# IRQF103C8.net
KiCad netlist of a schematic drawn in EAGLE
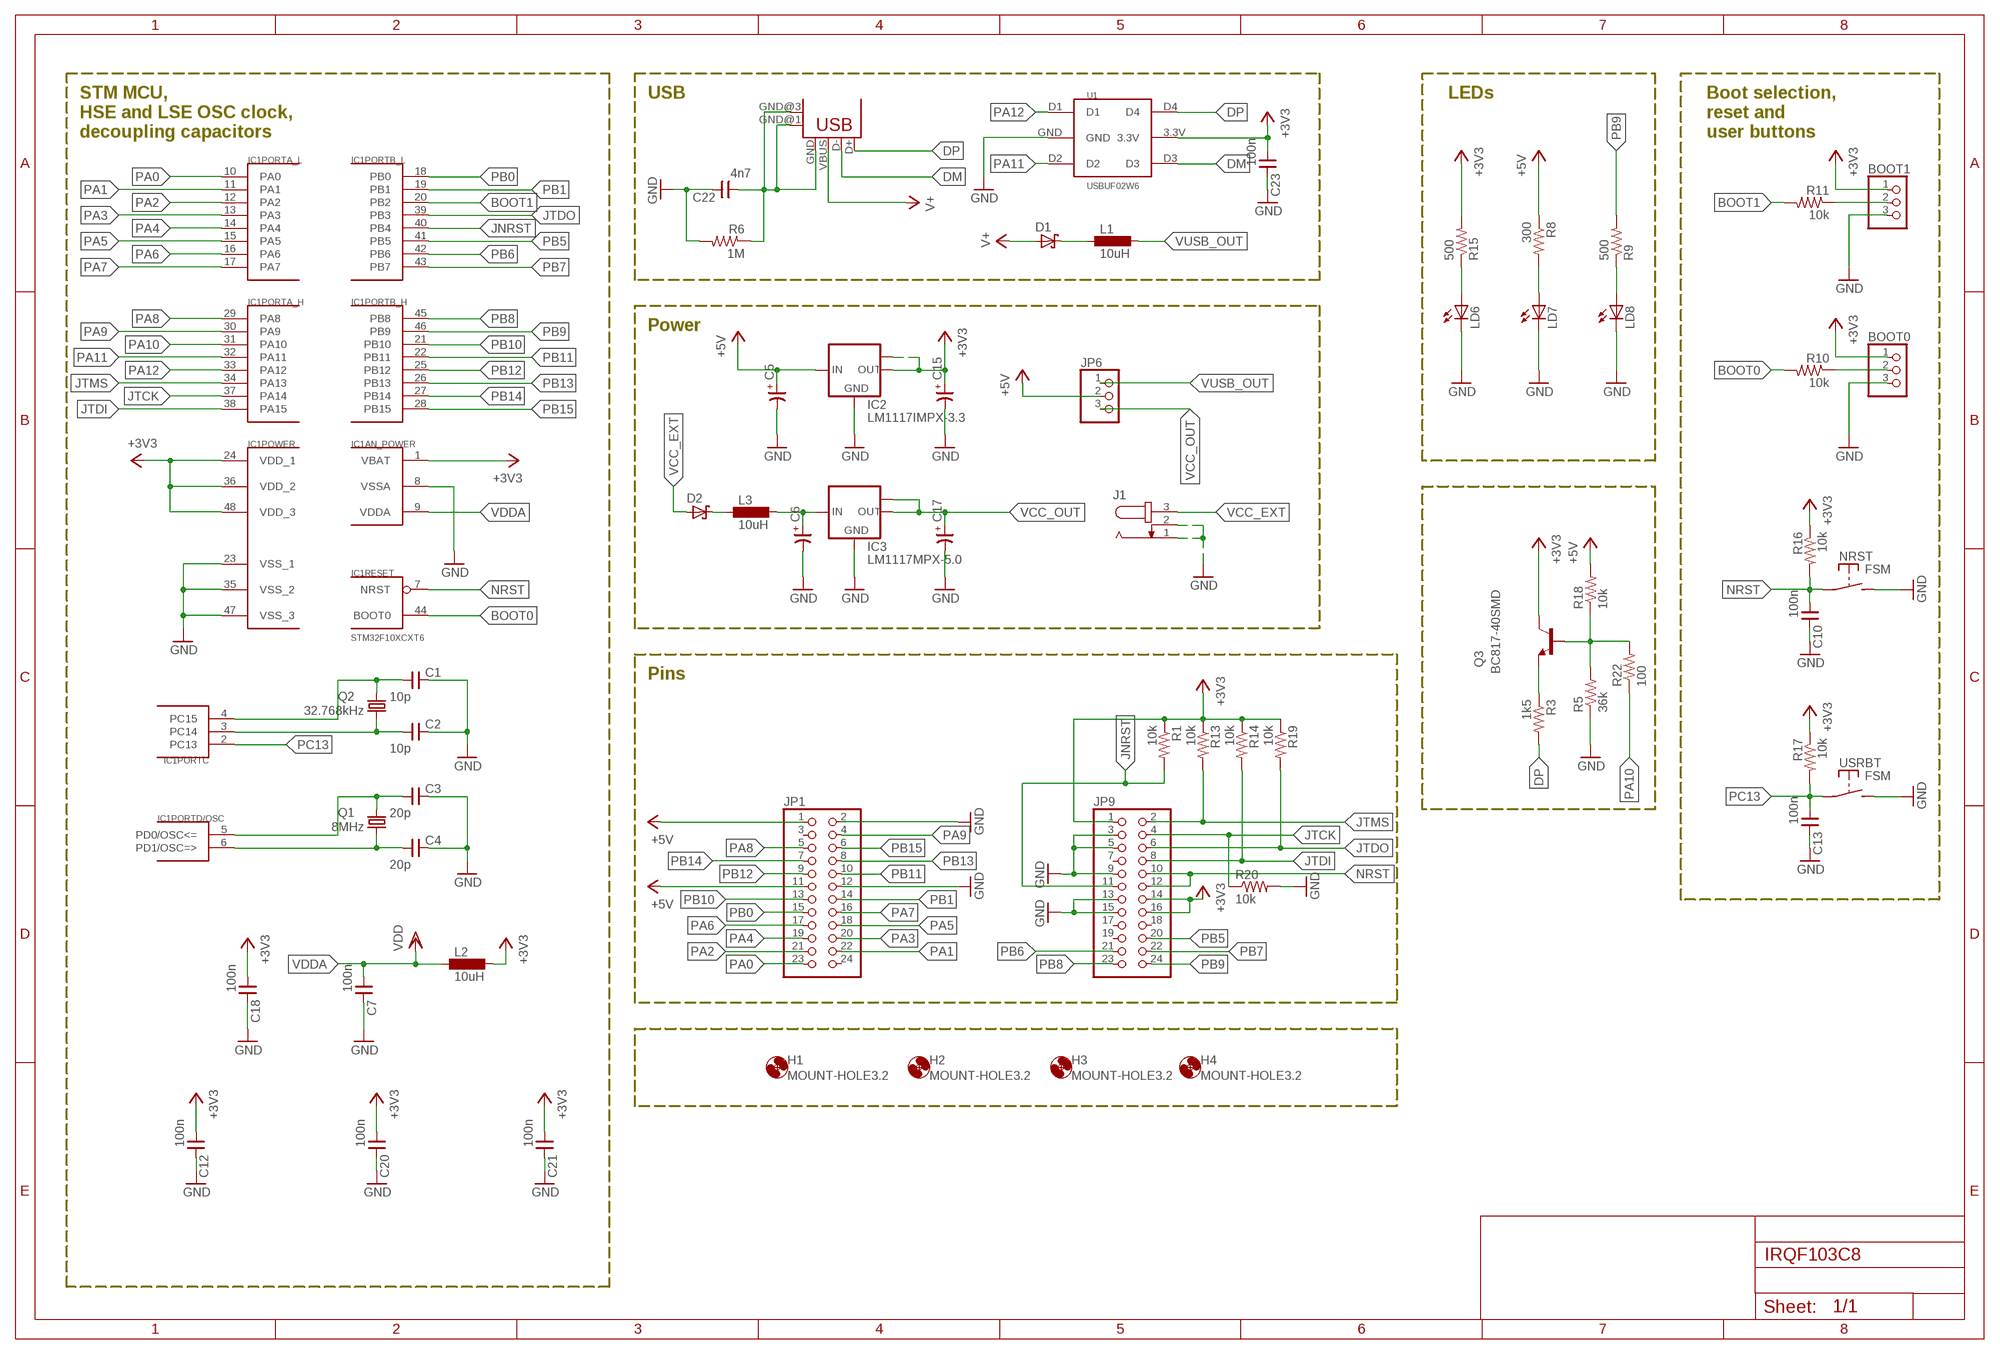
[diagram p0: schematic, sheet 1]

(export (version "E")
  (design (tool "Eeschema 10.0.6"))
  (components
    (comp (ref "BOOT0")
      (value "PINHD-1X3")
      (footprint "eagle-import:1X03")
      (libsource (lib "eagle-import") (part "PINHD-1X3"))
    )
    (comp (ref "BOOT1")
      (value "PINHD-1X3")
      (footprint "eagle-import:1X03")
      (libsource (lib "eagle-import") (part "PINHD-1X3"))
    )
    (comp (ref "C1")
      (value "10p")
      (footprint "eagle-import:0805")
      (libsource (lib "eagle-import") (part "CNP-0805"))
    )
    (comp (ref "C2")
      (value "10p")
      (footprint "eagle-import:0805")
      (libsource (lib "eagle-import") (part "CNP-0805"))
    )
    (comp (ref "C3")
      (value "20p")
      (footprint "eagle-import:0805")
      (libsource (lib "eagle-import") (part "CNP-0805"))
    )
    (comp (ref "C4")
      (value "20p")
      (footprint "eagle-import:0805")
      (libsource (lib "eagle-import") (part "CNP-0805"))
    )
    (comp (ref "C5")
      (value "CP-3258-TE-B")
      (footprint "eagle-import:3528-TE-B")
      (libsource (lib "eagle-import") (part "CP-3258-TE-B"))
    )
    (comp (ref "C6")
      (value "CP-3258-TE-B")
      (footprint "eagle-import:3528-TE-B")
      (libsource (lib "eagle-import") (part "CP-3258-TE-B"))
    )
    (comp (ref "C7")
      (value "100n")
      (footprint "eagle-import:0805")
      (libsource (lib "eagle-import") (part "CNP-0805"))
    )
    (comp (ref "C10")
      (value "100n")
      (footprint "eagle-import:0805")
      (libsource (lib "eagle-import") (part "CNP-0805"))
    )
    (comp (ref "C12")
      (value "100n")
      (footprint "eagle-import:0805")
      (libsource (lib "eagle-import") (part "CNP-0805"))
    )
    (comp (ref "C13")
      (value "100n")
      (footprint "eagle-import:0805")
      (libsource (lib "eagle-import") (part "CNP-0805"))
    )
    (comp (ref "C15")
      (value "CP-3216-TE-A")
      (footprint "eagle-import:3216-TE-A")
      (libsource (lib "eagle-import") (part "CP-3216-TE-A"))
    )
    (comp (ref "C17")
      (value "CP-3216-TE-A")
      (footprint "eagle-import:3216-TE-A")
      (libsource (lib "eagle-import") (part "CP-3216-TE-A"))
    )
    (comp (ref "C18")
      (value "100n")
      (footprint "eagle-import:0805")
      (libsource (lib "eagle-import") (part "CNP-0805"))
    )
    (comp (ref "C20")
      (value "100n")
      (footprint "eagle-import:0805")
      (libsource (lib "eagle-import") (part "CNP-0805"))
    )
    (comp (ref "C21")
      (value "100n")
      (footprint "eagle-import:0805")
      (libsource (lib "eagle-import") (part "CNP-0805"))
    )
    (comp (ref "C22")
      (value "4n7")
      (footprint "eagle-import:0805")
      (libsource (lib "eagle-import") (part "CNP-0805"))
    )
    (comp (ref "C23")
      (value "100n")
      (footprint "eagle-import:0805")
      (libsource (lib "eagle-import") (part "CNP-0805"))
    )
    (comp (ref "D1")
      (value "SCHOTTKY_SMA")
      (footprint "eagle-import:DIOM5326X292N")
      (libsource (lib "eagle-import") (part "SCHOTTKY_SMA"))
    )
    (comp (ref "D2")
      (value "SCHOTTKY_SMA")
      (footprint "eagle-import:DIOM5326X292N")
      (libsource (lib "eagle-import") (part "SCHOTTKY_SMA"))
    )
    (comp (ref "H1")
      (value "MOUNT-HOLE3.2")
      (footprint "eagle-import:3,2")
      (libsource (lib "eagle-import") (part "MOUNT-HOLE3.2"))
    )
    (comp (ref "H2")
      (value "MOUNT-HOLE3.2")
      (footprint "eagle-import:3,2")
      (libsource (lib "eagle-import") (part "MOUNT-HOLE3.2"))
    )
    (comp (ref "H3")
      (value "MOUNT-HOLE3.2")
      (footprint "eagle-import:3,2")
      (libsource (lib "eagle-import") (part "MOUNT-HOLE3.2"))
    )
    (comp (ref "H4")
      (value "MOUNT-HOLE3.2")
      (footprint "eagle-import:3,2")
      (libsource (lib "eagle-import") (part "MOUNT-HOLE3.2"))
    )
    (comp (ref "IC1")
      (value "STM32F10XCXT6")
      (footprint "eagle-import:TQFP48")
      (libsource (lib "eagle-import") (part "STM32F10XCXT6"))
    )
    (comp (ref "IC2")
      (value "LM1117IMPX-3.3")
      (footprint "eagle-import:SOT223")
      (libsource (lib "eagle-import") (part "LM1117IMPX-3.3"))
    )
    (comp (ref "IC3")
      (value "LM1117MPX-5.0")
      (footprint "eagle-import:SOT223")
      (libsource (lib "eagle-import") (part "LM1117MPX-5.0"))
    )
    (comp (ref "J1")
      (value "JACK-PLUG1")
      (footprint "eagle-import:SPC4078")
      (libsource (lib "eagle-import") (part "JACK-PLUG1"))
    )
    (comp (ref "JP1")
      (value "PINHD-2X12")
      (footprint "eagle-import:2X12")
      (libsource (lib "eagle-import") (part "PINHD-2X12"))
    )
    (comp (ref "JP6")
      (value "PINHD-1X3")
      (footprint "eagle-import:1X03")
      (libsource (lib "eagle-import") (part "PINHD-1X3"))
    )
    (comp (ref "JP9")
      (value "PINHD-2X12")
      (footprint "eagle-import:2X12")
      (libsource (lib "eagle-import") (part "PINHD-2X12"))
    )
    (comp (ref "L1")
      (value "10uH")
      (footprint "eagle-import:INDC1608X95N")
      (libsource (lib "eagle-import") (part "INDUCTOR_0603"))
    )
    (comp (ref "L2")
      (value "10uH")
      (footprint "eagle-import:INDC1608X95N")
      (libsource (lib "eagle-import") (part "INDUCTOR_0603"))
    )
    (comp (ref "L3")
      (value "10uH")
      (footprint "eagle-import:INDC1608X95N")
      (libsource (lib "eagle-import") (part "INDUCTOR_0603"))
    )
    (comp (ref "LD6")
      (value "LEDCHIPLED_0805")
      (footprint "eagle-import:CHIPLED_0805")
      (libsource (lib "eagle-import") (part "LEDCHIPLED_0805"))
    )
    (comp (ref "LD7")
      (value "LEDCHIPLED_0805")
      (footprint "eagle-import:CHIPLED_0805")
      (libsource (lib "eagle-import") (part "LEDCHIPLED_0805"))
    )
    (comp (ref "LD8")
      (value "LEDCHIPLED_0805")
      (footprint "eagle-import:CHIPLED_0805")
      (libsource (lib "eagle-import") (part "LEDCHIPLED_0805"))
    )
    (comp (ref "NRST")
      (value "FSM")
      (footprint "eagle-import:FSM")
      (libsource (lib "eagle-import") (part "FSM"))
    )
    (comp (ref "Q1")
      (value "8MHz")
      (footprint "eagle-import:HC49_S")
      (libsource (lib "eagle-import") (part "CRYTALHC49S"))
    )
    (comp (ref "Q2")
      (value "32.768kHz")
      (footprint "eagle-import:TC26H")
      (libsource (lib "eagle-import") (part "CRYTALTC26H"))
    )
    (comp (ref "Q3")
      (value "BC817-40SMD")
      (footprint "eagle-import:SOT23-BEC")
      (libsource (lib "eagle-import") (part "BC817SMD-40"))
    )
    (comp (ref "R1")
      (value "10k")
      (footprint "eagle-import:M0805")
      (libsource (lib "eagle-import") (part "R-US_M0805"))
    )
    (comp (ref "R3")
      (value "1k5")
      (footprint "eagle-import:M0805")
      (libsource (lib "eagle-import") (part "R-US_M0805"))
    )
    (comp (ref "R5")
      (value "36k")
      (footprint "eagle-import:M0805")
      (libsource (lib "eagle-import") (part "R-US_M0805"))
    )
    (comp (ref "R6")
      (value "1M")
      (footprint "eagle-import:M0805")
      (libsource (lib "eagle-import") (part "R-US_M0805"))
    )
    (comp (ref "R8")
      (value "300")
      (footprint "eagle-import:M0805")
      (libsource (lib "eagle-import") (part "R-US_M0805"))
    )
    (comp (ref "R9")
      (value "500")
      (footprint "eagle-import:M0805")
      (libsource (lib "eagle-import") (part "R-US_M0805"))
    )
    (comp (ref "R10")
      (value "10k")
      (footprint "eagle-import:M0805")
      (libsource (lib "eagle-import") (part "R-US_M0805"))
    )
    (comp (ref "R11")
      (value "10k")
      (footprint "eagle-import:M0805")
      (libsource (lib "eagle-import") (part "R-US_M0805"))
    )
    (comp (ref "R13")
      (value "10k")
      (footprint "eagle-import:M0805")
      (libsource (lib "eagle-import") (part "R-US_M0805"))
    )
    (comp (ref "R14")
      (value "10k")
      (footprint "eagle-import:M0805")
      (libsource (lib "eagle-import") (part "R-US_M0805"))
    )
    (comp (ref "R15")
      (value "500")
      (footprint "eagle-import:M0805")
      (libsource (lib "eagle-import") (part "R-US_M0805"))
    )
    (comp (ref "R16")
      (value "10k")
      (footprint "eagle-import:M0805")
      (libsource (lib "eagle-import") (part "R-US_M0805"))
    )
    (comp (ref "R17")
      (value "10k")
      (footprint "eagle-import:M0805")
      (libsource (lib "eagle-import") (part "R-US_M0805"))
    )
    (comp (ref "R18")
      (value "10k")
      (footprint "eagle-import:M0805")
      (libsource (lib "eagle-import") (part "R-US_M0805"))
    )
    (comp (ref "R19")
      (value "10k")
      (footprint "eagle-import:M0805")
      (libsource (lib "eagle-import") (part "R-US_M0805"))
    )
    (comp (ref "R20")
      (value "10k")
      (footprint "eagle-import:M0805")
      (libsource (lib "eagle-import") (part "R-US_M0805"))
    )
    (comp (ref "R22")
      (value "100")
      (footprint "eagle-import:M0805")
      (libsource (lib "eagle-import") (part "R-US_M0805"))
    )
    (comp (ref "U1")
      (value "USBUF02W6")
      (footprint "eagle-import:SOT23-6L")
      (libsource (lib "eagle-import") (part "USBUF02W6"))
    )
    (comp (ref "USB1")
      (value "USB-MB-S")
      (footprint "eagle-import:USB-MB-S")
      (libsource (lib "eagle-import") (part "USB-MB-S"))
    )
    (comp (ref "USRBT")
      (value "FSM")
      (footprint "eagle-import:FSM")
      (libsource (lib "eagle-import") (part "FSM"))
    )
  )
  (nets
    (net (code "1") (name "+3V3") (class "Default")
      (node (ref "BOOT0") (pin "1") (pinfunction "1_1") (pintype "passive"))
      (node (ref "BOOT1") (pin "1") (pinfunction "1_1") (pintype "passive"))
      (node (ref "C12") (pin "1") (pinfunction "1_1") (pintype "passive"))
      (node (ref "C15") (pin "+") (pinfunction "+_+") (pintype "passive"))
      (node (ref "C18") (pin "1") (pinfunction "1_1") (pintype "passive"))
      (node (ref "C20") (pin "1") (pinfunction "1_1") (pintype "passive"))
      (node (ref "C21") (pin "1") (pinfunction "1_1") (pintype "passive"))
      (node (ref "C23") (pin "1") (pinfunction "1_1") (pintype "passive"))
      (node (ref "IC1") (pin "1") (pinfunction "VBAT_1") (pintype "power_in"))
      (node (ref "IC1") (pin "24") (pinfunction "VDD_1_24") (pintype "power_in"))
      (node (ref "IC1") (pin "36") (pinfunction "VDD_2_36") (pintype "power_in"))
      (node (ref "IC1") (pin "48") (pinfunction "VDD_3_48") (pintype "power_in"))
      (node (ref "IC2") (pin "2") (pinfunction "OUT_2") (pintype "passive"))
      (node (ref "IC2") (pin "TAB") (pinfunction "OUT1_TAB") (pintype "passive"))
      (node (ref "JP9") (pin "1") (pinfunction "1_1") (pintype "passive"))
      (node (ref "JP9") (pin "14") (pinfunction "14_14") (pintype "passive"))
      (node (ref "JP9") (pin "16") (pinfunction "16_16") (pintype "passive"))
      (node (ref "L2") (pin "2") (pinfunction "2_2") (pintype "passive"))
      (node (ref "Q3") (pin "C") (pinfunction "C_C") (pintype "passive"))
      (node (ref "R1") (pin "1") (pinfunction "1_1") (pintype "passive"))
      (node (ref "R13") (pin "1") (pinfunction "1_1") (pintype "passive"))
      (node (ref "R14") (pin "1") (pinfunction "1_1") (pintype "passive"))
      (node (ref "R15") (pin "2") (pinfunction "2_2") (pintype "passive"))
      (node (ref "R16") (pin "1") (pinfunction "1_1") (pintype "passive"))
      (node (ref "R17") (pin "1") (pinfunction "1_1") (pintype "passive"))
      (node (ref "R19") (pin "1") (pinfunction "1_1") (pintype "passive"))
      (node (ref "U1") (pin "3.3V") (pinfunction "3.3V_3.3V") (pintype "bidirectional"))
    )
    (net (code "2") (name "+5V") (class "Default")
      (node (ref "C5") (pin "+") (pinfunction "+_+") (pintype "passive"))
      (node (ref "IC2") (pin "3") (pinfunction "IN_3") (pintype "input"))
      (node (ref "JP1") (pin "1") (pinfunction "1_1") (pintype "passive"))
      (node (ref "JP1") (pin "11") (pinfunction "11_11") (pintype "passive"))
      (node (ref "JP6") (pin "2") (pinfunction "2_2") (pintype "passive"))
      (node (ref "R18") (pin "2") (pinfunction "2_2") (pintype "passive"))
      (node (ref "R8") (pin "1") (pinfunction "1_1") (pintype "passive"))
    )
    (net (code "3") (name "BOOT0") (class "Default")
      (node (ref "IC1") (pin "44") (pinfunction "BOOT0_44") (pintype "input"))
      (node (ref "R10") (pin "2") (pinfunction "2_2") (pintype "passive"))
    )
    (net (code "4") (name "BOOT1") (class "Default")
      (node (ref "IC1") (pin "20") (pinfunction "PB2_20") (pintype "bidirectional"))
      (node (ref "R11") (pin "2") (pinfunction "2_2") (pintype "passive"))
    )
    (net (code "5") (name "DM") (class "Default")
      (node (ref "U1") (pin "D3") (pinfunction "D3_D3") (pintype "bidirectional"))
      (node (ref "USB1") (pin "D-") (pinfunction "D-_D-") (pintype "bidirectional"))
    )
    (net (code "6") (name "DP") (class "Default")
      (node (ref "R3") (pin "2") (pinfunction "2_2") (pintype "passive"))
      (node (ref "U1") (pin "D4") (pinfunction "D4_D4") (pintype "bidirectional"))
      (node (ref "USB1") (pin "D+") (pinfunction "D+_D+") (pintype "bidirectional"))
    )
    (net (code "7") (name "GND") (class "Default")
      (node (ref "BOOT0") (pin "3") (pinfunction "3_3") (pintype "passive"))
      (node (ref "BOOT1") (pin "3") (pinfunction "3_3") (pintype "passive"))
      (node (ref "C1") (pin "2") (pinfunction "2_2") (pintype "passive"))
      (node (ref "C10") (pin "2") (pinfunction "2_2") (pintype "passive"))
      (node (ref "C12") (pin "2") (pinfunction "2_2") (pintype "passive"))
      (node (ref "C13") (pin "2") (pinfunction "2_2") (pintype "passive"))
      (node (ref "C15") (pin "-") (pinfunction "-_-") (pintype "passive"))
      (node (ref "C17") (pin "-") (pinfunction "-_-") (pintype "passive"))
      (node (ref "C18") (pin "2") (pinfunction "2_2") (pintype "passive"))
      (node (ref "C2") (pin "2") (pinfunction "2_2") (pintype "passive"))
      (node (ref "C20") (pin "2") (pinfunction "2_2") (pintype "passive"))
      (node (ref "C21") (pin "2") (pinfunction "2_2") (pintype "passive"))
      (node (ref "C22") (pin "2") (pinfunction "2_2") (pintype "passive"))
      (node (ref "C23") (pin "2") (pinfunction "2_2") (pintype "passive"))
      (node (ref "C3") (pin "2") (pinfunction "2_2") (pintype "passive"))
      (node (ref "C4") (pin "2") (pinfunction "2_2") (pintype "passive"))
      (node (ref "C5") (pin "-") (pinfunction "-_-") (pintype "passive"))
      (node (ref "C6") (pin "-") (pinfunction "-_-") (pintype "passive"))
      (node (ref "C7") (pin "2") (pinfunction "2_2") (pintype "passive"))
      (node (ref "IC1") (pin "23") (pinfunction "VSS_1_23") (pintype "power_in"))
      (node (ref "IC1") (pin "35") (pinfunction "VSS_2_35") (pintype "power_in"))
      (node (ref "IC1") (pin "47") (pinfunction "VSS_3_47") (pintype "power_in"))
      (node (ref "IC1") (pin "8") (pinfunction "VSSA_8") (pintype "power_in"))
      (node (ref "IC2") (pin "1") (pinfunction "GND_1") (pintype "input"))
      (node (ref "IC3") (pin "1") (pinfunction "GND_1") (pintype "input"))
      (node (ref "J1") (pin "1") (pinfunction "1_1") (pintype "passive"))
      (node (ref "J1") (pin "2") (pinfunction "2_2") (pintype "passive"))
      (node (ref "JP1") (pin "12") (pinfunction "12_12") (pintype "passive"))
      (node (ref "JP1") (pin "2") (pinfunction "2_2") (pintype "passive"))
      (node (ref "JP9") (pin "13") (pinfunction "13_13") (pintype "passive"))
      (node (ref "JP9") (pin "15") (pinfunction "15_15") (pintype "passive"))
      (node (ref "JP9") (pin "3") (pinfunction "3_3") (pintype "passive"))
      (node (ref "JP9") (pin "5") (pinfunction "5_5") (pintype "passive"))
      (node (ref "JP9") (pin "9") (pinfunction "9_9") (pintype "passive"))
      (node (ref "LD6") (pin "C") (pinfunction "C_C") (pintype "passive"))
      (node (ref "LD7") (pin "C") (pinfunction "C_C") (pintype "passive"))
      (node (ref "LD8") (pin "C") (pinfunction "C_C") (pintype "passive"))
      (node (ref "NRST") (pin "P$2") (pinfunction "S_P$2") (pintype "passive"))
      (node (ref "R20") (pin "2") (pinfunction "2_2") (pintype "passive"))
      (node (ref "R5") (pin "1") (pinfunction "1_1") (pintype "passive"))
      (node (ref "R6") (pin "2") (pinfunction "2_2") (pintype "passive"))
      (node (ref "U1") (pin "GND") (pinfunction "GND_GND") (pintype "bidirectional"))
      (node (ref "USRBT") (pin "P$2") (pinfunction "S_P$2") (pintype "passive"))
    )
    (net (code "8") (name "JNRST") (class "Default")
      (node (ref "IC1") (pin "40") (pinfunction "PB4_40") (pintype "bidirectional"))
      (node (ref "JP9") (pin "11") (pinfunction "11_11") (pintype "passive"))
      (node (ref "R1") (pin "2") (pinfunction "2_2") (pintype "passive"))
    )
    (net (code "9") (name "JTCK") (class "Default")
      (node (ref "IC1") (pin "37") (pinfunction "PA14_37") (pintype "bidirectional"))
      (node (ref "JP9") (pin "4") (pinfunction "4_4") (pintype "passive"))
      (node (ref "R20") (pin "1") (pinfunction "1_1") (pintype "passive"))
    )
    (net (code "10") (name "JTDI") (class "Default")
      (node (ref "IC1") (pin "38") (pinfunction "PA15_38") (pintype "bidirectional"))
      (node (ref "JP9") (pin "8") (pinfunction "8_8") (pintype "passive"))
      (node (ref "R14") (pin "2") (pinfunction "2_2") (pintype "passive"))
    )
    (net (code "11") (name "JTDO") (class "Default")
      (node (ref "IC1") (pin "39") (pinfunction "PB3_39") (pintype "bidirectional"))
      (node (ref "JP9") (pin "6") (pinfunction "6_6") (pintype "passive"))
      (node (ref "R19") (pin "2") (pinfunction "2_2") (pintype "passive"))
    )
    (net (code "12") (name "JTMS") (class "Default")
      (node (ref "IC1") (pin "34") (pinfunction "PA13_34") (pintype "bidirectional"))
      (node (ref "JP9") (pin "2") (pinfunction "2_2") (pintype "passive"))
      (node (ref "R13") (pin "2") (pinfunction "2_2") (pintype "passive"))
    )
    (net (code "13") (name "NRST") (class "Default")
      (node (ref "C10") (pin "1") (pinfunction "1_1") (pintype "passive"))
      (node (ref "IC1") (pin "7") (pinfunction "NRST_7") (pintype "input"))
      (node (ref "JP9") (pin "10") (pinfunction "10_10") (pintype "passive"))
      (node (ref "JP9") (pin "12") (pinfunction "12_12") (pintype "passive"))
      (node (ref "NRST") (pin "P$1") (pinfunction "P_P$1") (pintype "passive"))
      (node (ref "R16") (pin "2") (pinfunction "2_2") (pintype "passive"))
    )
    (net (code "14") (name "Net-(BOOT0-Pad2)") (class "Default")
      (node (ref "BOOT0") (pin "2") (pinfunction "2_2") (pintype "passive"))
      (node (ref "R10") (pin "1") (pinfunction "1_1") (pintype "passive"))
    )
    (net (code "15") (name "Net-(BOOT1-Pad2)") (class "Default")
      (node (ref "BOOT1") (pin "2") (pinfunction "2_2") (pintype "passive"))
      (node (ref "R11") (pin "1") (pinfunction "1_1") (pintype "passive"))
    )
    (net (code "16") (name "Net-(C22-Pad1)") (class "Default")
      (node (ref "C22") (pin "1") (pinfunction "1_1") (pintype "passive"))
      (node (ref "R6") (pin "1") (pinfunction "1_1") (pintype "passive"))
      (node (ref "USB1") (pin "GND") (pinfunction "GND_GND") (pintype "bidirectional"))
      (node (ref "USB1") (pin "GND@1") (pinfunction "GND_GND@1") (pintype "bidirectional"))
      (node (ref "USB1") (pin "GND@3") (pinfunction "GND_GND@3") (pintype "bidirectional"))
    )
    (net (code "17") (name "Net-(D1-PadK)") (class "Default")
      (node (ref "D1") (pin "K") (pinfunction "K_K") (pintype "passive"))
      (node (ref "L1") (pin "1") (pinfunction "1_1") (pintype "passive"))
    )
    (net (code "18") (name "Net-(D2-PadK)") (class "Default")
      (node (ref "D2") (pin "K") (pinfunction "K_K") (pintype "passive"))
      (node (ref "L3") (pin "1") (pinfunction "1_1") (pintype "passive"))
    )
    (net (code "19") (name "Net-(IC1F-PC14)") (class "Default")
      (node (ref "C2") (pin "1") (pinfunction "1_1") (pintype "passive"))
      (node (ref "IC1") (pin "3") (pinfunction "PC14_3") (pintype "bidirectional"))
      (node (ref "Q2") (pin "1") (pinfunction "1_1") (pintype "passive"))
    )
    (net (code "20") (name "Net-(IC1F-PC15)") (class "Default")
      (node (ref "C1") (pin "1") (pinfunction "1_1") (pintype "passive"))
      (node (ref "IC1") (pin "4") (pinfunction "PC15_4") (pintype "bidirectional"))
      (node (ref "Q2") (pin "2") (pinfunction "2_2") (pintype "passive"))
    )
    (net (code "21") (name "Net-(IC1G-PD0{slash}OSC<=)") (class "Default")
      (node (ref "C3") (pin "1") (pinfunction "1_1") (pintype "passive"))
      (node (ref "IC1") (pin "5") (pinfunction "PD0/OSC<=_5") (pintype "bidirectional"))
      (node (ref "Q1") (pin "2") (pinfunction "2_2") (pintype "passive"))
    )
    (net (code "22") (name "Net-(IC1G-PD1{slash}OSC=>)") (class "Default")
      (node (ref "C4") (pin "1") (pinfunction "1_1") (pintype "passive"))
      (node (ref "IC1") (pin "6") (pinfunction "PD1/OSC=>_6") (pintype "bidirectional"))
      (node (ref "Q1") (pin "1") (pinfunction "1_1") (pintype "passive"))
    )
    (net (code "23") (name "Net-(IC3-IN)") (class "Default")
      (node (ref "C6") (pin "+") (pinfunction "+_+") (pintype "passive"))
      (node (ref "IC3") (pin "3") (pinfunction "IN_3") (pintype "input"))
      (node (ref "L3") (pin "2") (pinfunction "2_2") (pintype "passive"))
    )
    (net (code "24") (name "Net-(LD6-PadA)") (class "Default")
      (node (ref "LD6") (pin "A") (pinfunction "A_A") (pintype "passive"))
      (node (ref "R15") (pin "1") (pinfunction "1_1") (pintype "passive"))
    )
    (net (code "25") (name "Net-(LD7-PadA)") (class "Default")
      (node (ref "LD7") (pin "A") (pinfunction "A_A") (pintype "passive"))
      (node (ref "R8") (pin "2") (pinfunction "2_2") (pintype "passive"))
    )
    (net (code "26") (name "Net-(LD8-PadA)") (class "Default")
      (node (ref "LD8") (pin "A") (pinfunction "A_A") (pintype "passive"))
      (node (ref "R9") (pin "1") (pinfunction "1_1") (pintype "passive"))
    )
    (net (code "27") (name "Net-(Q3-PadB)") (class "Default")
      (node (ref "Q3") (pin "B") (pinfunction "B_B") (pintype "passive"))
      (node (ref "R18") (pin "1") (pinfunction "1_1") (pintype "passive"))
      (node (ref "R22") (pin "2") (pinfunction "2_2") (pintype "passive"))
      (node (ref "R5") (pin "2") (pinfunction "2_2") (pintype "passive"))
    )
    (net (code "28") (name "Net-(Q3-PadE)") (class "Default")
      (node (ref "Q3") (pin "E") (pinfunction "E_E") (pintype "passive"))
      (node (ref "R3") (pin "1") (pinfunction "1_1") (pintype "passive"))
    )
    (net (code "29") (name "PA0") (class "Default")
      (node (ref "IC1") (pin "10") (pinfunction "PA0_10") (pintype "bidirectional"))
      (node (ref "JP1") (pin "23") (pinfunction "23_23") (pintype "passive"))
    )
    (net (code "30") (name "PA1") (class "Default")
      (node (ref "IC1") (pin "11") (pinfunction "PA1_11") (pintype "bidirectional"))
      (node (ref "JP1") (pin "22") (pinfunction "22_22") (pintype "passive"))
    )
    (net (code "31") (name "PA2") (class "Default")
      (node (ref "IC1") (pin "12") (pinfunction "PA2_12") (pintype "bidirectional"))
      (node (ref "JP1") (pin "21") (pinfunction "21_21") (pintype "passive"))
    )
    (net (code "32") (name "PA3") (class "Default")
      (node (ref "IC1") (pin "13") (pinfunction "PA3_13") (pintype "bidirectional"))
      (node (ref "JP1") (pin "20") (pinfunction "20_20") (pintype "passive"))
    )
    (net (code "33") (name "PA4") (class "Default")
      (node (ref "IC1") (pin "14") (pinfunction "PA4_14") (pintype "bidirectional"))
      (node (ref "JP1") (pin "19") (pinfunction "19_19") (pintype "passive"))
    )
    (net (code "34") (name "PA5") (class "Default")
      (node (ref "IC1") (pin "15") (pinfunction "PA5_15") (pintype "bidirectional"))
      (node (ref "JP1") (pin "18") (pinfunction "18_18") (pintype "passive"))
    )
    (net (code "35") (name "PA6") (class "Default")
      (node (ref "IC1") (pin "16") (pinfunction "PA6_16") (pintype "bidirectional"))
      (node (ref "JP1") (pin "17") (pinfunction "17_17") (pintype "passive"))
    )
    (net (code "36") (name "PA7") (class "Default")
      (node (ref "IC1") (pin "17") (pinfunction "PA7_17") (pintype "bidirectional"))
      (node (ref "JP1") (pin "16") (pinfunction "16_16") (pintype "passive"))
    )
    (net (code "37") (name "PA8") (class "Default")
      (node (ref "IC1") (pin "29") (pinfunction "PA8_29") (pintype "bidirectional"))
      (node (ref "JP1") (pin "5") (pinfunction "5_5") (pintype "passive"))
    )
    (net (code "38") (name "PA9") (class "Default")
      (node (ref "IC1") (pin "30") (pinfunction "PA9_30") (pintype "bidirectional"))
      (node (ref "JP1") (pin "4") (pinfunction "4_4") (pintype "passive"))
    )
    (net (code "39") (name "PA10") (class "Default")
      (node (ref "IC1") (pin "31") (pinfunction "PA10_31") (pintype "bidirectional"))
      (node (ref "R22") (pin "1") (pinfunction "1_1") (pintype "passive"))
    )
    (net (code "40") (name "PA11") (class "Default")
      (node (ref "IC1") (pin "32") (pinfunction "PA11_32") (pintype "bidirectional"))
      (node (ref "U1") (pin "D2") (pinfunction "D2_D2") (pintype "bidirectional"))
    )
    (net (code "41") (name "PA12") (class "Default")
      (node (ref "IC1") (pin "33") (pinfunction "PA12_33") (pintype "bidirectional"))
      (node (ref "U1") (pin "D1") (pinfunction "D1_D1") (pintype "bidirectional"))
    )
    (net (code "42") (name "PB0") (class "Default")
      (node (ref "IC1") (pin "18") (pinfunction "PB0_18") (pintype "bidirectional"))
      (node (ref "JP1") (pin "15") (pinfunction "15_15") (pintype "passive"))
    )
    (net (code "43") (name "PB1") (class "Default")
      (node (ref "IC1") (pin "19") (pinfunction "PB1_19") (pintype "bidirectional"))
      (node (ref "JP1") (pin "14") (pinfunction "14_14") (pintype "passive"))
    )
    (net (code "44") (name "PB5") (class "Default")
      (node (ref "IC1") (pin "41") (pinfunction "PB5_41") (pintype "bidirectional"))
      (node (ref "JP9") (pin "20") (pinfunction "20_20") (pintype "passive"))
    )
    (net (code "45") (name "PB6") (class "Default")
      (node (ref "IC1") (pin "42") (pinfunction "PB6_42") (pintype "bidirectional"))
      (node (ref "JP9") (pin "21") (pinfunction "21_21") (pintype "passive"))
    )
    (net (code "46") (name "PB7") (class "Default")
      (node (ref "IC1") (pin "43") (pinfunction "PB7_43") (pintype "bidirectional"))
      (node (ref "JP9") (pin "22") (pinfunction "22_22") (pintype "passive"))
    )
    (net (code "47") (name "PB8") (class "Default")
      (node (ref "IC1") (pin "45") (pinfunction "PB8_45") (pintype "bidirectional"))
      (node (ref "JP9") (pin "23") (pinfunction "23_23") (pintype "passive"))
    )
    (net (code "48") (name "PB9") (class "Default")
      (node (ref "IC1") (pin "46") (pinfunction "PB9_46") (pintype "bidirectional"))
      (node (ref "JP9") (pin "24") (pinfunction "24_24") (pintype "passive"))
      (node (ref "R9") (pin "2") (pinfunction "2_2") (pintype "passive"))
    )
    (net (code "49") (name "PB10") (class "Default")
      (node (ref "IC1") (pin "21") (pinfunction "PB10_21") (pintype "bidirectional"))
      (node (ref "JP1") (pin "13") (pinfunction "13_13") (pintype "passive"))
    )
    (net (code "50") (name "PB11") (class "Default")
      (node (ref "IC1") (pin "22") (pinfunction "PB11_22") (pintype "bidirectional"))
      (node (ref "JP1") (pin "10") (pinfunction "10_10") (pintype "passive"))
    )
    (net (code "51") (name "PB12") (class "Default")
      (node (ref "IC1") (pin "25") (pinfunction "PB12_25") (pintype "bidirectional"))
      (node (ref "JP1") (pin "9") (pinfunction "9_9") (pintype "passive"))
    )
    (net (code "52") (name "PB13") (class "Default")
      (node (ref "IC1") (pin "26") (pinfunction "PB13_26") (pintype "bidirectional"))
      (node (ref "JP1") (pin "8") (pinfunction "8_8") (pintype "passive"))
    )
    (net (code "53") (name "PB14") (class "Default")
      (node (ref "IC1") (pin "27") (pinfunction "PB14_27") (pintype "bidirectional"))
      (node (ref "JP1") (pin "7") (pinfunction "7_7") (pintype "passive"))
    )
    (net (code "54") (name "PB15") (class "Default")
      (node (ref "IC1") (pin "28") (pinfunction "PB15_28") (pintype "bidirectional"))
      (node (ref "JP1") (pin "6") (pinfunction "6_6") (pintype "passive"))
    )
    (net (code "55") (name "PC13") (class "Default")
      (node (ref "C13") (pin "1") (pinfunction "1_1") (pintype "passive"))
      (node (ref "IC1") (pin "2") (pinfunction "PC13_2") (pintype "bidirectional"))
      (node (ref "R17") (pin "2") (pinfunction "2_2") (pintype "passive"))
      (node (ref "USRBT") (pin "P$1") (pinfunction "P_P$1") (pintype "passive"))
    )
    (net (code "56") (name "V+") (class "Default")
      (node (ref "D1") (pin "A") (pinfunction "A_A") (pintype "passive"))
      (node (ref "USB1") (pin "VBUS") (pinfunction "VBUS_VBUS") (pintype "bidirectional"))
    )
    (net (code "57") (name "VCC_EXT") (class "Default")
      (node (ref "D2") (pin "A") (pinfunction "A_A") (pintype "passive"))
      (node (ref "J1") (pin "3") (pinfunction "3_3") (pintype "passive"))
    )
    (net (code "58") (name "VCC_OUT") (class "Default")
      (node (ref "C17") (pin "+") (pinfunction "+_+") (pintype "passive"))
      (node (ref "IC3") (pin "2") (pinfunction "OUT_2") (pintype "passive"))
      (node (ref "IC3") (pin "TAB") (pinfunction "OUT1_TAB") (pintype "passive"))
      (node (ref "JP6") (pin "3") (pinfunction "3_3") (pintype "passive"))
    )
    (net (code "59") (name "VDDA") (class "Default")
      (node (ref "C7") (pin "1") (pinfunction "1_1") (pintype "passive"))
      (node (ref "IC1") (pin "9") (pinfunction "VDDA_9") (pintype "power_in"))
      (node (ref "L2") (pin "1") (pinfunction "1_1") (pintype "passive"))
    )
    (net (code "60") (name "VUSB_OUT") (class "Default")
      (node (ref "JP6") (pin "1") (pinfunction "1_1") (pintype "passive"))
      (node (ref "L1") (pin "2") (pinfunction "2_2") (pintype "passive"))
    )
    (net (code "61") (name "unconnected-(JP1-Pad3)") (class "Default")
      (node (ref "JP1") (pin "3") (pinfunction "3_3") (pintype "passive"))
    )
    (net (code "62") (name "unconnected-(JP1-Pad24)") (class "Default")
      (node (ref "JP1") (pin "24") (pinfunction "24_24") (pintype "passive"))
    )
    (net (code "63") (name "unconnected-(JP9-Pad7)") (class "Default")
      (node (ref "JP9") (pin "7") (pinfunction "7_7") (pintype "passive"))
    )
    (net (code "64") (name "unconnected-(JP9-Pad17)") (class "Default")
      (node (ref "JP9") (pin "17") (pinfunction "17_17") (pintype "passive"))
    )
    (net (code "65") (name "unconnected-(JP9-Pad18)") (class "Default")
      (node (ref "JP9") (pin "18") (pinfunction "18_18") (pintype "passive"))
    )
    (net (code "66") (name "unconnected-(JP9-Pad19)") (class "Default")
      (node (ref "JP9") (pin "19") (pinfunction "19_19") (pintype "passive"))
    )
  )
)
